# Morpheus_LED2.net
KiCad netlist of a schematic drawn in Altium Designer
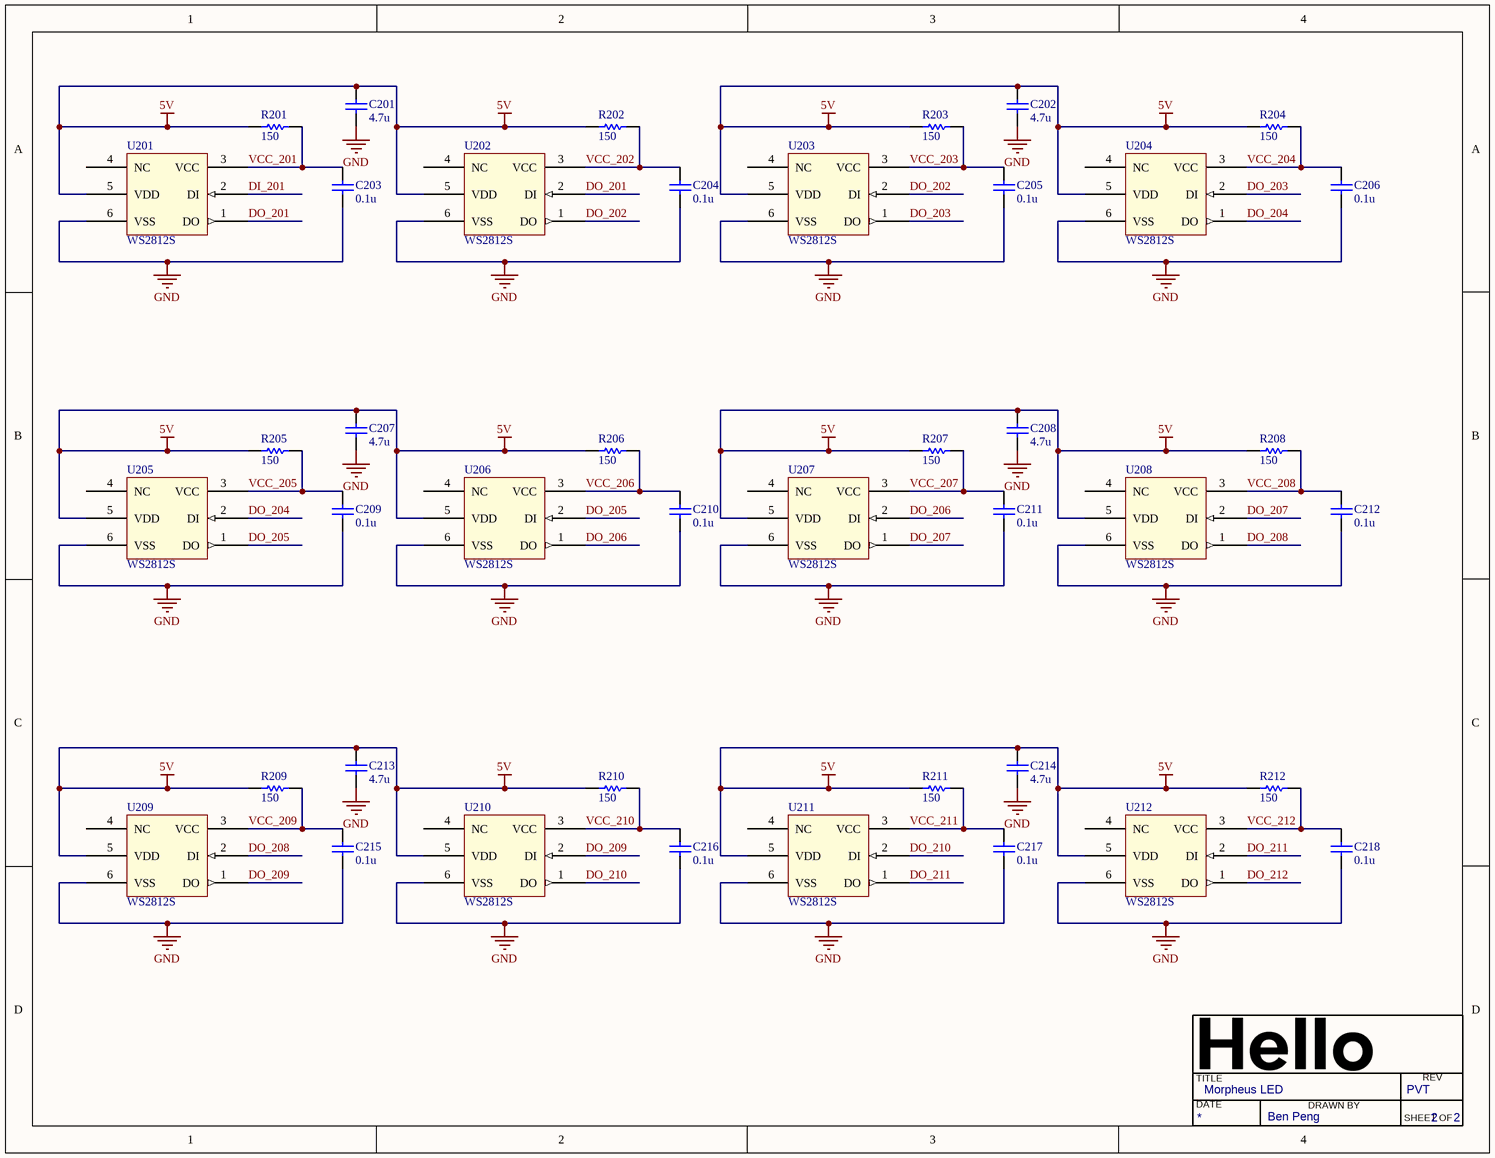
[diagram p0: Morpheus_LED2.SchDoc]

(export (version "E")
  (design (tool "Eeschema 10.0.6"))
  (components
    (comp (ref "C201")
      (value "4.7u")
      (footprint "CAP0402_SENSE_DVT")
      (description "CAP CER 4.7UF 10V 10% X5R 0402")
      (fields (field (name "TOLERANCE") "10%") (field (name "VOLTAGE") "10V"))
      (libsource (lib "Morpheus_pill") (part "C_4.7u_10_10_JB_0402"))
    )
    (comp (ref "C202")
      (value "4.7u")
      (footprint "CAP0402_SENSE_DVT")
      (description "CAP CER 4.7UF 10V 10% X5R 0402")
      (fields (field (name "TOLERANCE") "10%") (field (name "VOLTAGE") "10V"))
      (libsource (lib "Morpheus_pill") (part "C_4.7u_10_10_JB_0402"))
    )
    (comp (ref "C203")
      (value "0.1u")
      (footprint "CAP0402_SENSE_DVT")
      (description "CAP CER 0.1UF 50V 10% X7R 0402")
      (fields (field (name "TOLERANCE") "10%") (field (name "VOLTAGE") "50V"))
      (libsource (lib "Morpheus_pill") (part "C_0.1u_10_50_X7R_0402"))
    )
    (comp (ref "C204")
      (value "0.1u")
      (footprint "CAP0402_SENSE_DVT")
      (description "CAP CER 0.1UF 50V 10% X7R 0402")
      (fields (field (name "TOLERANCE") "10%") (field (name "VOLTAGE") "50V"))
      (libsource (lib "Morpheus_pill") (part "C_0.1u_10_50_X7R_0402"))
    )
    (comp (ref "C205")
      (value "0.1u")
      (footprint "CAP0402_SENSE_DVT")
      (description "CAP CER 0.1UF 50V 10% X7R 0402")
      (fields (field (name "TOLERANCE") "10%") (field (name "VOLTAGE") "50V"))
      (libsource (lib "Morpheus_pill") (part "C_0.1u_10_50_X7R_0402"))
    )
    (comp (ref "C206")
      (value "0.1u")
      (footprint "CAP0402_SENSE_DVT")
      (description "CAP CER 0.1UF 50V 10% X7R 0402")
      (fields (field (name "TOLERANCE") "10%") (field (name "VOLTAGE") "50V"))
      (libsource (lib "Morpheus_pill") (part "C_0.1u_10_50_X7R_0402"))
    )
    (comp (ref "C207")
      (value "4.7u")
      (footprint "CAP0402_SENSE_DVT")
      (description "CAP CER 4.7UF 10V 10% X5R 0402")
      (fields (field (name "TOLERANCE") "10%") (field (name "VOLTAGE") "10V"))
      (libsource (lib "Morpheus_pill") (part "C_4.7u_10_10_JB_0402"))
    )
    (comp (ref "C208")
      (value "4.7u")
      (footprint "CAP0402_SENSE_DVT")
      (description "CAP CER 4.7UF 10V 10% X5R 0402")
      (fields (field (name "TOLERANCE") "10%") (field (name "VOLTAGE") "10V"))
      (libsource (lib "Morpheus_pill") (part "C_4.7u_10_10_JB_0402"))
    )
    (comp (ref "C209")
      (value "0.1u")
      (footprint "CAP0402_SENSE_DVT")
      (description "CAP CER 0.1UF 50V 10% X7R 0402")
      (fields (field (name "TOLERANCE") "10%") (field (name "VOLTAGE") "50V"))
      (libsource (lib "Morpheus_pill") (part "C_0.1u_10_50_X7R_0402"))
    )
    (comp (ref "C210")
      (value "0.1u")
      (footprint "CAP0402_SENSE_DVT")
      (description "CAP CER 0.1UF 50V 10% X7R 0402")
      (fields (field (name "TOLERANCE") "10%") (field (name "VOLTAGE") "50V"))
      (libsource (lib "Morpheus_pill") (part "C_0.1u_10_50_X7R_0402"))
    )
    (comp (ref "C211")
      (value "0.1u")
      (footprint "CAP0402_SENSE_DVT")
      (description "CAP CER 0.1UF 50V 10% X7R 0402")
      (fields (field (name "TOLERANCE") "10%") (field (name "VOLTAGE") "50V"))
      (libsource (lib "Morpheus_pill") (part "C_0.1u_10_50_X7R_0402"))
    )
    (comp (ref "C212")
      (value "0.1u")
      (footprint "CAP0402_SENSE_DVT")
      (description "CAP CER 0.1UF 50V 10% X7R 0402")
      (fields (field (name "TOLERANCE") "10%") (field (name "VOLTAGE") "50V"))
      (libsource (lib "Morpheus_pill") (part "C_0.1u_10_50_X7R_0402"))
    )
    (comp (ref "C213")
      (value "4.7u")
      (footprint "CAP0402_SENSE_DVT")
      (description "CAP CER 4.7UF 10V 10% X5R 0402")
      (fields (field (name "TOLERANCE") "10%") (field (name "VOLTAGE") "10V"))
      (libsource (lib "Morpheus_pill") (part "C_4.7u_10_10_JB_0402"))
    )
    (comp (ref "C214")
      (value "4.7u")
      (footprint "CAP0402_SENSE_DVT")
      (description "CAP CER 4.7UF 10V 10% X5R 0402")
      (fields (field (name "TOLERANCE") "10%") (field (name "VOLTAGE") "10V"))
      (libsource (lib "Morpheus_pill") (part "C_4.7u_10_10_JB_0402"))
    )
    (comp (ref "C215")
      (value "0.1u")
      (footprint "CAP0402_SENSE_DVT")
      (description "CAP CER 0.1UF 50V 10% X7R 0402")
      (fields (field (name "TOLERANCE") "10%") (field (name "VOLTAGE") "50V"))
      (libsource (lib "Morpheus_pill") (part "C_0.1u_10_50_X7R_0402"))
    )
    (comp (ref "C216")
      (value "0.1u")
      (footprint "CAP0402_SENSE_DVT")
      (description "CAP CER 0.1UF 50V 10% X7R 0402")
      (fields (field (name "TOLERANCE") "10%") (field (name "VOLTAGE") "50V"))
      (libsource (lib "Morpheus_pill") (part "C_0.1u_10_50_X7R_0402"))
    )
    (comp (ref "C217")
      (value "0.1u")
      (footprint "CAP0402_SENSE_DVT")
      (description "CAP CER 0.1UF 50V 10% X7R 0402")
      (fields (field (name "TOLERANCE") "10%") (field (name "VOLTAGE") "50V"))
      (libsource (lib "Morpheus_pill") (part "C_0.1u_10_50_X7R_0402"))
    )
    (comp (ref "C218")
      (value "0.1u")
      (footprint "CAP0402_SENSE_DVT")
      (description "CAP CER 0.1UF 50V 10% X7R 0402")
      (fields (field (name "TOLERANCE") "10%") (field (name "VOLTAGE") "50V"))
      (libsource (lib "Morpheus_pill") (part "C_0.1u_10_50_X7R_0402"))
    )
    (comp (ref "R201")
      (value "150")
      (footprint "RES0402_SENSE_DVT")
      (description "RES SMD 150 OHM 1% 1/16W 0402")
      (fields (field (name "TOLERANCE") "1 %") (field (name "POWER") "1/16 W"))
      (libsource (lib "Morpheus_pill") (part "R_150_1_0.1_0402"))
    )
    (comp (ref "R202")
      (value "150")
      (footprint "RES0402_SENSE_DVT")
      (description "RES SMD 150 OHM 1% 1/16W 0402")
      (fields (field (name "TOLERANCE") "1 %") (field (name "POWER") "1/16 W"))
      (libsource (lib "Morpheus_pill") (part "R_150_1_0.1_0402"))
    )
    (comp (ref "R203")
      (value "150")
      (footprint "RES0402_SENSE_DVT")
      (description "RES SMD 150 OHM 1% 1/16W 0402")
      (fields (field (name "TOLERANCE") "1 %") (field (name "POWER") "1/16 W"))
      (libsource (lib "Morpheus_pill") (part "R_150_1_0.1_0402"))
    )
    (comp (ref "R204")
      (value "150")
      (footprint "RES0402_SENSE_DVT")
      (description "RES SMD 150 OHM 1% 1/16W 0402")
      (fields (field (name "TOLERANCE") "1 %") (field (name "POWER") "1/16 W"))
      (libsource (lib "Morpheus_pill") (part "R_150_1_0.1_0402"))
    )
    (comp (ref "R205")
      (value "150")
      (footprint "RES0402_SENSE_DVT")
      (description "RES SMD 150 OHM 1% 1/16W 0402")
      (fields (field (name "TOLERANCE") "1 %") (field (name "POWER") "1/16 W"))
      (libsource (lib "Morpheus_pill") (part "R_150_1_0.1_0402"))
    )
    (comp (ref "R206")
      (value "150")
      (footprint "RES0402_SENSE_DVT")
      (description "RES SMD 150 OHM 1% 1/16W 0402")
      (fields (field (name "TOLERANCE") "1 %") (field (name "POWER") "1/16 W"))
      (libsource (lib "Morpheus_pill") (part "R_150_1_0.1_0402"))
    )
    (comp (ref "R207")
      (value "150")
      (footprint "RES0402_SENSE_DVT")
      (description "RES SMD 150 OHM 1% 1/16W 0402")
      (fields (field (name "TOLERANCE") "1 %") (field (name "POWER") "1/16 W"))
      (libsource (lib "Morpheus_pill") (part "R_150_1_0.1_0402"))
    )
    (comp (ref "R208")
      (value "150")
      (footprint "RES0402_SENSE_DVT")
      (description "RES SMD 150 OHM 1% 1/16W 0402")
      (fields (field (name "TOLERANCE") "1 %") (field (name "POWER") "1/16 W"))
      (libsource (lib "Morpheus_pill") (part "R_150_1_0.1_0402"))
    )
    (comp (ref "R209")
      (value "150")
      (footprint "RES0402_SENSE_DVT")
      (description "RES SMD 150 OHM 1% 1/16W 0402")
      (fields (field (name "TOLERANCE") "1 %") (field (name "POWER") "1/16 W"))
      (libsource (lib "Morpheus_pill") (part "R_150_1_0.1_0402"))
    )
    (comp (ref "R210")
      (value "150")
      (footprint "RES0402_SENSE_DVT")
      (description "RES SMD 150 OHM 1% 1/16W 0402")
      (fields (field (name "TOLERANCE") "1 %") (field (name "POWER") "1/16 W"))
      (libsource (lib "Morpheus_pill") (part "R_150_1_0.1_0402"))
    )
    (comp (ref "R211")
      (value "150")
      (footprint "RES0402_SENSE_DVT")
      (description "RES SMD 150 OHM 1% 1/16W 0402")
      (fields (field (name "TOLERANCE") "1 %") (field (name "POWER") "1/16 W"))
      (libsource (lib "Morpheus_pill") (part "R_150_1_0.1_0402"))
    )
    (comp (ref "R212")
      (value "150")
      (footprint "RES0402_SENSE_DVT")
      (description "RES SMD 150 OHM 1% 1/16W 0402")
      (fields (field (name "TOLERANCE") "1 %") (field (name "POWER") "1/16 W"))
      (libsource (lib "Morpheus_pill") (part "R_150_1_0.1_0402"))
    )
    (comp (ref "U201")
      (value "WS2812S")
      (footprint "6PIN_WS2812")
      (description "WS2812S Intelligent control LED integrated light source")
      (libsource (lib "Morpheus_pill") (part "WS2812S"))
    )
    (comp (ref "U202")
      (value "WS2812S")
      (footprint "6PIN_WS2812")
      (description "WS2812S Intelligent control LED integrated light source")
      (libsource (lib "Morpheus_pill") (part "WS2812S"))
    )
    (comp (ref "U203")
      (value "WS2812S")
      (footprint "6PIN_WS2812")
      (description "WS2812S Intelligent control LED integrated light source")
      (libsource (lib "Morpheus_pill") (part "WS2812S"))
    )
    (comp (ref "U204")
      (value "WS2812S")
      (footprint "6PIN_WS2812")
      (description "WS2812S Intelligent control LED integrated light source")
      (libsource (lib "Morpheus_pill") (part "WS2812S"))
    )
    (comp (ref "U205")
      (value "WS2812S")
      (footprint "6PIN_WS2812")
      (description "WS2812S Intelligent control LED integrated light source")
      (libsource (lib "Morpheus_pill") (part "WS2812S"))
    )
    (comp (ref "U206")
      (value "WS2812S")
      (footprint "6PIN_WS2812")
      (description "WS2812S Intelligent control LED integrated light source")
      (libsource (lib "Morpheus_pill") (part "WS2812S"))
    )
    (comp (ref "U207")
      (value "WS2812S")
      (footprint "6PIN_WS2812")
      (description "WS2812S Intelligent control LED integrated light source")
      (libsource (lib "Morpheus_pill") (part "WS2812S"))
    )
    (comp (ref "U208")
      (value "WS2812S")
      (footprint "6PIN_WS2812")
      (description "WS2812S Intelligent control LED integrated light source")
      (libsource (lib "Morpheus_pill") (part "WS2812S"))
    )
    (comp (ref "U209")
      (value "WS2812S")
      (footprint "6PIN_WS2812")
      (description "WS2812S Intelligent control LED integrated light source")
      (libsource (lib "Morpheus_pill") (part "WS2812S"))
    )
    (comp (ref "U210")
      (value "WS2812S")
      (footprint "6PIN_WS2812")
      (description "WS2812S Intelligent control LED integrated light source")
      (libsource (lib "Morpheus_pill") (part "WS2812S"))
    )
    (comp (ref "U211")
      (value "WS2812S")
      (footprint "6PIN_WS2812")
      (description "WS2812S Intelligent control LED integrated light source")
      (libsource (lib "Morpheus_pill") (part "WS2812S"))
    )
    (comp (ref "U212")
      (value "WS2812S")
      (footprint "6PIN_WS2812")
      (description "WS2812S Intelligent control LED integrated light source")
      (libsource (lib "Morpheus_pill") (part "WS2812S"))
    )
  )
  (nets
    (net (code "1") (name "/DI_201") (class "Default")
      (node (ref "U201") (pin "2") (pinfunction "DI_2") (pintype "input"))
    )
    (net (code "2") (name "/DO_201") (class "Default")
      (node (ref "U201") (pin "1") (pinfunction "DO_1") (pintype "output"))
      (node (ref "U202") (pin "2") (pinfunction "DI_2") (pintype "input"))
    )
    (net (code "3") (name "/DO_202") (class "Default")
      (node (ref "U202") (pin "1") (pinfunction "DO_1") (pintype "output"))
      (node (ref "U203") (pin "2") (pinfunction "DI_2") (pintype "input"))
    )
    (net (code "4") (name "/DO_203") (class "Default")
      (node (ref "U203") (pin "1") (pinfunction "DO_1") (pintype "output"))
      (node (ref "U204") (pin "2") (pinfunction "DI_2") (pintype "input"))
    )
    (net (code "5") (name "/DO_204") (class "Default")
      (node (ref "U204") (pin "1") (pinfunction "DO_1") (pintype "output"))
      (node (ref "U205") (pin "2") (pinfunction "DI_2") (pintype "input"))
    )
    (net (code "6") (name "/DO_205") (class "Default")
      (node (ref "U205") (pin "1") (pinfunction "DO_1") (pintype "output"))
      (node (ref "U206") (pin "2") (pinfunction "DI_2") (pintype "input"))
    )
    (net (code "7") (name "/DO_206") (class "Default")
      (node (ref "U206") (pin "1") (pinfunction "DO_1") (pintype "output"))
      (node (ref "U207") (pin "2") (pinfunction "DI_2") (pintype "input"))
    )
    (net (code "8") (name "/DO_207") (class "Default")
      (node (ref "U207") (pin "1") (pinfunction "DO_1") (pintype "output"))
      (node (ref "U208") (pin "2") (pinfunction "DI_2") (pintype "input"))
    )
    (net (code "9") (name "/DO_208") (class "Default")
      (node (ref "U208") (pin "1") (pinfunction "DO_1") (pintype "output"))
      (node (ref "U209") (pin "2") (pinfunction "DI_2") (pintype "input"))
    )
    (net (code "10") (name "/DO_209") (class "Default")
      (node (ref "U209") (pin "1") (pinfunction "DO_1") (pintype "output"))
      (node (ref "U210") (pin "2") (pinfunction "DI_2") (pintype "input"))
    )
    (net (code "11") (name "/DO_210") (class "Default")
      (node (ref "U210") (pin "1") (pinfunction "DO_1") (pintype "output"))
      (node (ref "U211") (pin "2") (pinfunction "DI_2") (pintype "input"))
    )
    (net (code "12") (name "/DO_211") (class "Default")
      (node (ref "U211") (pin "1") (pinfunction "DO_1") (pintype "output"))
      (node (ref "U212") (pin "2") (pinfunction "DI_2") (pintype "input"))
    )
    (net (code "13") (name "/DO_212") (class "Default")
      (node (ref "U212") (pin "1") (pinfunction "DO_1") (pintype "output"))
    )
    (net (code "14") (name "/VCC_201") (class "Default")
      (node (ref "C203") (pin "2") (pinfunction "2_2") (pintype "passive"))
      (node (ref "R201") (pin "1") (pinfunction "1_1") (pintype "passive"))
      (node (ref "U201") (pin "3") (pinfunction "VCC_3") (pintype "power_in"))
    )
    (net (code "15") (name "/VCC_202") (class "Default")
      (node (ref "C204") (pin "2") (pinfunction "2_2") (pintype "passive"))
      (node (ref "R202") (pin "1") (pinfunction "1_1") (pintype "passive"))
      (node (ref "U202") (pin "3") (pinfunction "VCC_3") (pintype "power_in"))
    )
    (net (code "16") (name "/VCC_203") (class "Default")
      (node (ref "C205") (pin "2") (pinfunction "2_2") (pintype "passive"))
      (node (ref "R203") (pin "1") (pinfunction "1_1") (pintype "passive"))
      (node (ref "U203") (pin "3") (pinfunction "VCC_3") (pintype "power_in"))
    )
    (net (code "17") (name "/VCC_204") (class "Default")
      (node (ref "C206") (pin "2") (pinfunction "2_2") (pintype "passive"))
      (node (ref "R204") (pin "1") (pinfunction "1_1") (pintype "passive"))
      (node (ref "U204") (pin "3") (pinfunction "VCC_3") (pintype "power_in"))
    )
    (net (code "18") (name "/VCC_205") (class "Default")
      (node (ref "C209") (pin "2") (pinfunction "2_2") (pintype "passive"))
      (node (ref "R205") (pin "1") (pinfunction "1_1") (pintype "passive"))
      (node (ref "U205") (pin "3") (pinfunction "VCC_3") (pintype "power_in"))
    )
    (net (code "19") (name "/VCC_206") (class "Default")
      (node (ref "C210") (pin "2") (pinfunction "2_2") (pintype "passive"))
      (node (ref "R206") (pin "1") (pinfunction "1_1") (pintype "passive"))
      (node (ref "U206") (pin "3") (pinfunction "VCC_3") (pintype "power_in"))
    )
    (net (code "20") (name "/VCC_207") (class "Default")
      (node (ref "C211") (pin "2") (pinfunction "2_2") (pintype "passive"))
      (node (ref "R207") (pin "1") (pinfunction "1_1") (pintype "passive"))
      (node (ref "U207") (pin "3") (pinfunction "VCC_3") (pintype "power_in"))
    )
    (net (code "21") (name "/VCC_208") (class "Default")
      (node (ref "C212") (pin "2") (pinfunction "2_2") (pintype "passive"))
      (node (ref "R208") (pin "1") (pinfunction "1_1") (pintype "passive"))
      (node (ref "U208") (pin "3") (pinfunction "VCC_3") (pintype "power_in"))
    )
    (net (code "22") (name "/VCC_209") (class "Default")
      (node (ref "C215") (pin "2") (pinfunction "2_2") (pintype "passive"))
      (node (ref "R209") (pin "1") (pinfunction "1_1") (pintype "passive"))
      (node (ref "U209") (pin "3") (pinfunction "VCC_3") (pintype "power_in"))
    )
    (net (code "23") (name "/VCC_210") (class "Default")
      (node (ref "C216") (pin "2") (pinfunction "2_2") (pintype "passive"))
      (node (ref "R210") (pin "1") (pinfunction "1_1") (pintype "passive"))
      (node (ref "U210") (pin "3") (pinfunction "VCC_3") (pintype "power_in"))
    )
    (net (code "24") (name "/VCC_211") (class "Default")
      (node (ref "C217") (pin "2") (pinfunction "2_2") (pintype "passive"))
      (node (ref "R211") (pin "1") (pinfunction "1_1") (pintype "passive"))
      (node (ref "U211") (pin "3") (pinfunction "VCC_3") (pintype "power_in"))
    )
    (net (code "25") (name "/VCC_212") (class "Default")
      (node (ref "C218") (pin "2") (pinfunction "2_2") (pintype "passive"))
      (node (ref "R212") (pin "1") (pinfunction "1_1") (pintype "passive"))
      (node (ref "U212") (pin "3") (pinfunction "VCC_3") (pintype "power_in"))
    )
    (net (code "26") (name "5V") (class "Default")
      (node (ref "C201") (pin "2") (pinfunction "2_2") (pintype "passive"))
      (node (ref "C202") (pin "2") (pinfunction "2_2") (pintype "passive"))
      (node (ref "C207") (pin "2") (pinfunction "2_2") (pintype "passive"))
      (node (ref "C208") (pin "2") (pinfunction "2_2") (pintype "passive"))
      (node (ref "C213") (pin "2") (pinfunction "2_2") (pintype "passive"))
      (node (ref "C214") (pin "2") (pinfunction "2_2") (pintype "passive"))
      (node (ref "R201") (pin "2") (pinfunction "2_2") (pintype "passive"))
      (node (ref "R202") (pin "2") (pinfunction "2_2") (pintype "passive"))
      (node (ref "R203") (pin "2") (pinfunction "2_2") (pintype "passive"))
      (node (ref "R204") (pin "2") (pinfunction "2_2") (pintype "passive"))
      (node (ref "R205") (pin "2") (pinfunction "2_2") (pintype "passive"))
      (node (ref "R206") (pin "2") (pinfunction "2_2") (pintype "passive"))
      (node (ref "R207") (pin "2") (pinfunction "2_2") (pintype "passive"))
      (node (ref "R208") (pin "2") (pinfunction "2_2") (pintype "passive"))
      (node (ref "R209") (pin "2") (pinfunction "2_2") (pintype "passive"))
      (node (ref "R210") (pin "2") (pinfunction "2_2") (pintype "passive"))
      (node (ref "R211") (pin "2") (pinfunction "2_2") (pintype "passive"))
      (node (ref "R212") (pin "2") (pinfunction "2_2") (pintype "passive"))
      (node (ref "U201") (pin "5") (pinfunction "VDD_5") (pintype "power_in"))
      (node (ref "U202") (pin "5") (pinfunction "VDD_5") (pintype "power_in"))
      (node (ref "U203") (pin "5") (pinfunction "VDD_5") (pintype "power_in"))
      (node (ref "U204") (pin "5") (pinfunction "VDD_5") (pintype "power_in"))
      (node (ref "U205") (pin "5") (pinfunction "VDD_5") (pintype "power_in"))
      (node (ref "U206") (pin "5") (pinfunction "VDD_5") (pintype "power_in"))
      (node (ref "U207") (pin "5") (pinfunction "VDD_5") (pintype "power_in"))
      (node (ref "U208") (pin "5") (pinfunction "VDD_5") (pintype "power_in"))
      (node (ref "U209") (pin "5") (pinfunction "VDD_5") (pintype "power_in"))
      (node (ref "U210") (pin "5") (pinfunction "VDD_5") (pintype "power_in"))
      (node (ref "U211") (pin "5") (pinfunction "VDD_5") (pintype "power_in"))
      (node (ref "U212") (pin "5") (pinfunction "VDD_5") (pintype "power_in"))
    )
    (net (code "27") (name "GND") (class "Default")
      (node (ref "C201") (pin "1") (pinfunction "1_1") (pintype "passive"))
      (node (ref "C202") (pin "1") (pinfunction "1_1") (pintype "passive"))
      (node (ref "C203") (pin "1") (pinfunction "1_1") (pintype "passive"))
      (node (ref "C204") (pin "1") (pinfunction "1_1") (pintype "passive"))
      (node (ref "C205") (pin "1") (pinfunction "1_1") (pintype "passive"))
      (node (ref "C206") (pin "1") (pinfunction "1_1") (pintype "passive"))
      (node (ref "C207") (pin "1") (pinfunction "1_1") (pintype "passive"))
      (node (ref "C208") (pin "1") (pinfunction "1_1") (pintype "passive"))
      (node (ref "C209") (pin "1") (pinfunction "1_1") (pintype "passive"))
      (node (ref "C210") (pin "1") (pinfunction "1_1") (pintype "passive"))
      (node (ref "C211") (pin "1") (pinfunction "1_1") (pintype "passive"))
      (node (ref "C212") (pin "1") (pinfunction "1_1") (pintype "passive"))
      (node (ref "C213") (pin "1") (pinfunction "1_1") (pintype "passive"))
      (node (ref "C214") (pin "1") (pinfunction "1_1") (pintype "passive"))
      (node (ref "C215") (pin "1") (pinfunction "1_1") (pintype "passive"))
      (node (ref "C216") (pin "1") (pinfunction "1_1") (pintype "passive"))
      (node (ref "C217") (pin "1") (pinfunction "1_1") (pintype "passive"))
      (node (ref "C218") (pin "1") (pinfunction "1_1") (pintype "passive"))
      (node (ref "U201") (pin "6") (pinfunction "VSS_6") (pintype "power_in"))
      (node (ref "U202") (pin "6") (pinfunction "VSS_6") (pintype "power_in"))
      (node (ref "U203") (pin "6") (pinfunction "VSS_6") (pintype "power_in"))
      (node (ref "U204") (pin "6") (pinfunction "VSS_6") (pintype "power_in"))
      (node (ref "U205") (pin "6") (pinfunction "VSS_6") (pintype "power_in"))
      (node (ref "U206") (pin "6") (pinfunction "VSS_6") (pintype "power_in"))
      (node (ref "U207") (pin "6") (pinfunction "VSS_6") (pintype "power_in"))
      (node (ref "U208") (pin "6") (pinfunction "VSS_6") (pintype "power_in"))
      (node (ref "U209") (pin "6") (pinfunction "VSS_6") (pintype "power_in"))
      (node (ref "U210") (pin "6") (pinfunction "VSS_6") (pintype "power_in"))
      (node (ref "U211") (pin "6") (pinfunction "VSS_6") (pintype "power_in"))
      (node (ref "U212") (pin "6") (pinfunction "VSS_6") (pintype "power_in"))
    )
    (net (code "28") (name "unconnected-(U201-NC-Pad4)") (class "Default")
      (node (ref "U201") (pin "4") (pinfunction "NC_4") (pintype "passive"))
    )
    (net (code "29") (name "unconnected-(U202-NC-Pad4)") (class "Default")
      (node (ref "U202") (pin "4") (pinfunction "NC_4") (pintype "passive"))
    )
    (net (code "30") (name "unconnected-(U203-NC-Pad4)") (class "Default")
      (node (ref "U203") (pin "4") (pinfunction "NC_4") (pintype "passive"))
    )
    (net (code "31") (name "unconnected-(U204-NC-Pad4)") (class "Default")
      (node (ref "U204") (pin "4") (pinfunction "NC_4") (pintype "passive"))
    )
    (net (code "32") (name "unconnected-(U205-NC-Pad4)") (class "Default")
      (node (ref "U205") (pin "4") (pinfunction "NC_4") (pintype "passive"))
    )
    (net (code "33") (name "unconnected-(U206-NC-Pad4)") (class "Default")
      (node (ref "U206") (pin "4") (pinfunction "NC_4") (pintype "passive"))
    )
    (net (code "34") (name "unconnected-(U207-NC-Pad4)") (class "Default")
      (node (ref "U207") (pin "4") (pinfunction "NC_4") (pintype "passive"))
    )
    (net (code "35") (name "unconnected-(U208-NC-Pad4)") (class "Default")
      (node (ref "U208") (pin "4") (pinfunction "NC_4") (pintype "passive"))
    )
    (net (code "36") (name "unconnected-(U209-NC-Pad4)") (class "Default")
      (node (ref "U209") (pin "4") (pinfunction "NC_4") (pintype "passive"))
    )
    (net (code "37") (name "unconnected-(U210-NC-Pad4)") (class "Default")
      (node (ref "U210") (pin "4") (pinfunction "NC_4") (pintype "passive"))
    )
    (net (code "38") (name "unconnected-(U211-NC-Pad4)") (class "Default")
      (node (ref "U211") (pin "4") (pinfunction "NC_4") (pintype "passive"))
    )
    (net (code "39") (name "unconnected-(U212-NC-Pad4)") (class "Default")
      (node (ref "U212") (pin "4") (pinfunction "NC_4") (pintype "passive"))
    )
  )
)
